# Overview.net
KiCad netlist of a schematic drawn in Altium Designer
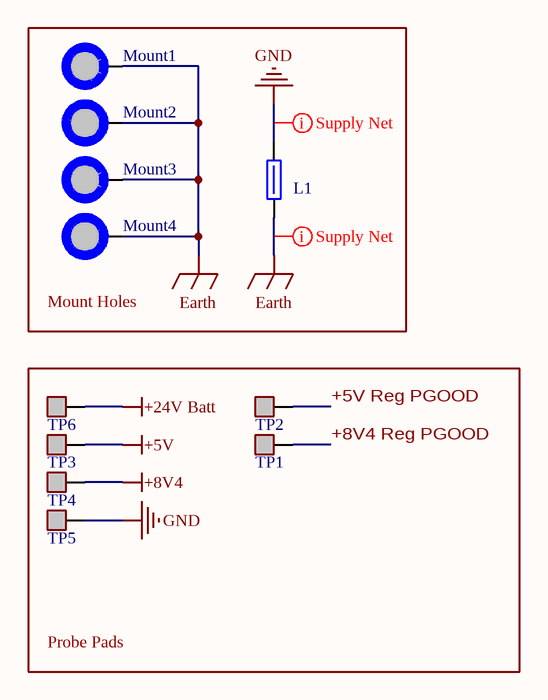
[diagram p0: Overview.SchDoc]

(export (version "E")
  (design (tool "Eeschema 10.0.6"))
  (components
    (comp (ref "L1")
      (value "652-MH2029-300Y")
      (footprint "[Ferrite] SMD Bead 0805 (1)")
      (libsource (lib "RADM Components") (part "[Ferrite] SMD Ferrite Bead (1)"))
    )
    (comp (ref "Mount1")
      (value "M3 Mount Hole")
      (footprint "[Mount] M3 Mount Hole")
      (description "Place at least 4.5mm from board edge. Plated.")
      (libsource (lib "RADM Connectors") (part "[Mount] M3 Mount Hole"))
    )
    (comp (ref "Mount2")
      (value "M3 Mount Hole")
      (footprint "[Mount] M3 Mount Hole")
      (description "Place at least 4.5mm from board edge. Plated.")
      (libsource (lib "RADM Connectors") (part "[Mount] M3 Mount Hole"))
    )
    (comp (ref "Mount3")
      (value "M3 Mount Hole")
      (footprint "[Mount] M3 Mount Hole")
      (description "Place at least 4.5mm from board edge. Plated.")
      (libsource (lib "RADM Connectors") (part "[Mount] M3 Mount Hole"))
    )
    (comp (ref "Mount4")
      (value "M3 Mount Hole")
      (footprint "[Mount] M3 Mount Hole")
      (description "Place at least 4.5mm from board edge. Plated.")
      (libsource (lib "RADM Connectors") (part "[Mount] M3 Mount Hole"))
    )
    (comp (ref "TP1")
      (value "Probe Pad")
      (footprint "[Probe] Touch Pad")
      (libsource (lib "RADM Connectors") (part "[Probe] Touch Pad"))
    )
    (comp (ref "TP2")
      (value "Probe Pad")
      (footprint "[Probe] Touch Pad")
      (libsource (lib "RADM Connectors") (part "[Probe] Touch Pad"))
    )
    (comp (ref "TP3")
      (value "Probe Pad")
      (footprint "[Probe] Touch Pad")
      (libsource (lib "RADM Connectors") (part "[Probe] Touch Pad"))
    )
    (comp (ref "TP4")
      (value "Probe Pad")
      (footprint "[Probe] Touch Pad")
      (libsource (lib "RADM Connectors") (part "[Probe] Touch Pad"))
    )
    (comp (ref "TP5")
      (value "Probe Pad")
      (footprint "[Probe] Touch Pad")
      (libsource (lib "RADM Connectors") (part "[Probe] Touch Pad"))
    )
    (comp (ref "TP6")
      (value "Probe Pad")
      (footprint "[Probe] Touch Pad")
      (libsource (lib "RADM Connectors") (part "[Probe] Touch Pad"))
    )
  )
  (nets
    (net (code "1") (name "+5V") (class "Default")
      (node (ref "TP3") (pin "1") (pinfunction "1_1") (pintype "passive"))
    )
    (net (code "2") (name "+8V4") (class "Default")
      (node (ref "TP4") (pin "1") (pinfunction "1_1") (pintype "passive"))
    )
    (net (code "3") (name "+24V Batt") (class "Default")
      (node (ref "TP6") (pin "1") (pinfunction "1_1") (pintype "passive"))
    )
    (net (code "4") (name "/+5V Reg PGOOD") (class "Default")
      (node (ref "TP2") (pin "1") (pinfunction "1_1") (pintype "passive"))
    )
    (net (code "5") (name "/+8V4 Reg PGOOD") (class "Default")
      (node (ref "TP1") (pin "1") (pinfunction "1_1") (pintype "passive"))
    )
    (net (code "6") (name "Earth") (class "Default")
      (node (ref "L1") (pin "1") (pinfunction "1_1") (pintype "passive"))
      (node (ref "Mount1") (pin "1") (pintype "power_in"))
      (node (ref "Mount2") (pin "1") (pintype "power_in"))
      (node (ref "Mount3") (pin "1") (pintype "power_in"))
      (node (ref "Mount4") (pin "1") (pintype "power_in"))
    )
    (net (code "7") (name "GND") (class "Default")
      (node (ref "L1") (pin "2") (pinfunction "2_2") (pintype "passive"))
      (node (ref "TP5") (pin "1") (pinfunction "1_1") (pintype "passive"))
    )
  )
)
